# edr.net
KiCad netlist of a schematic drawn in EAGLE
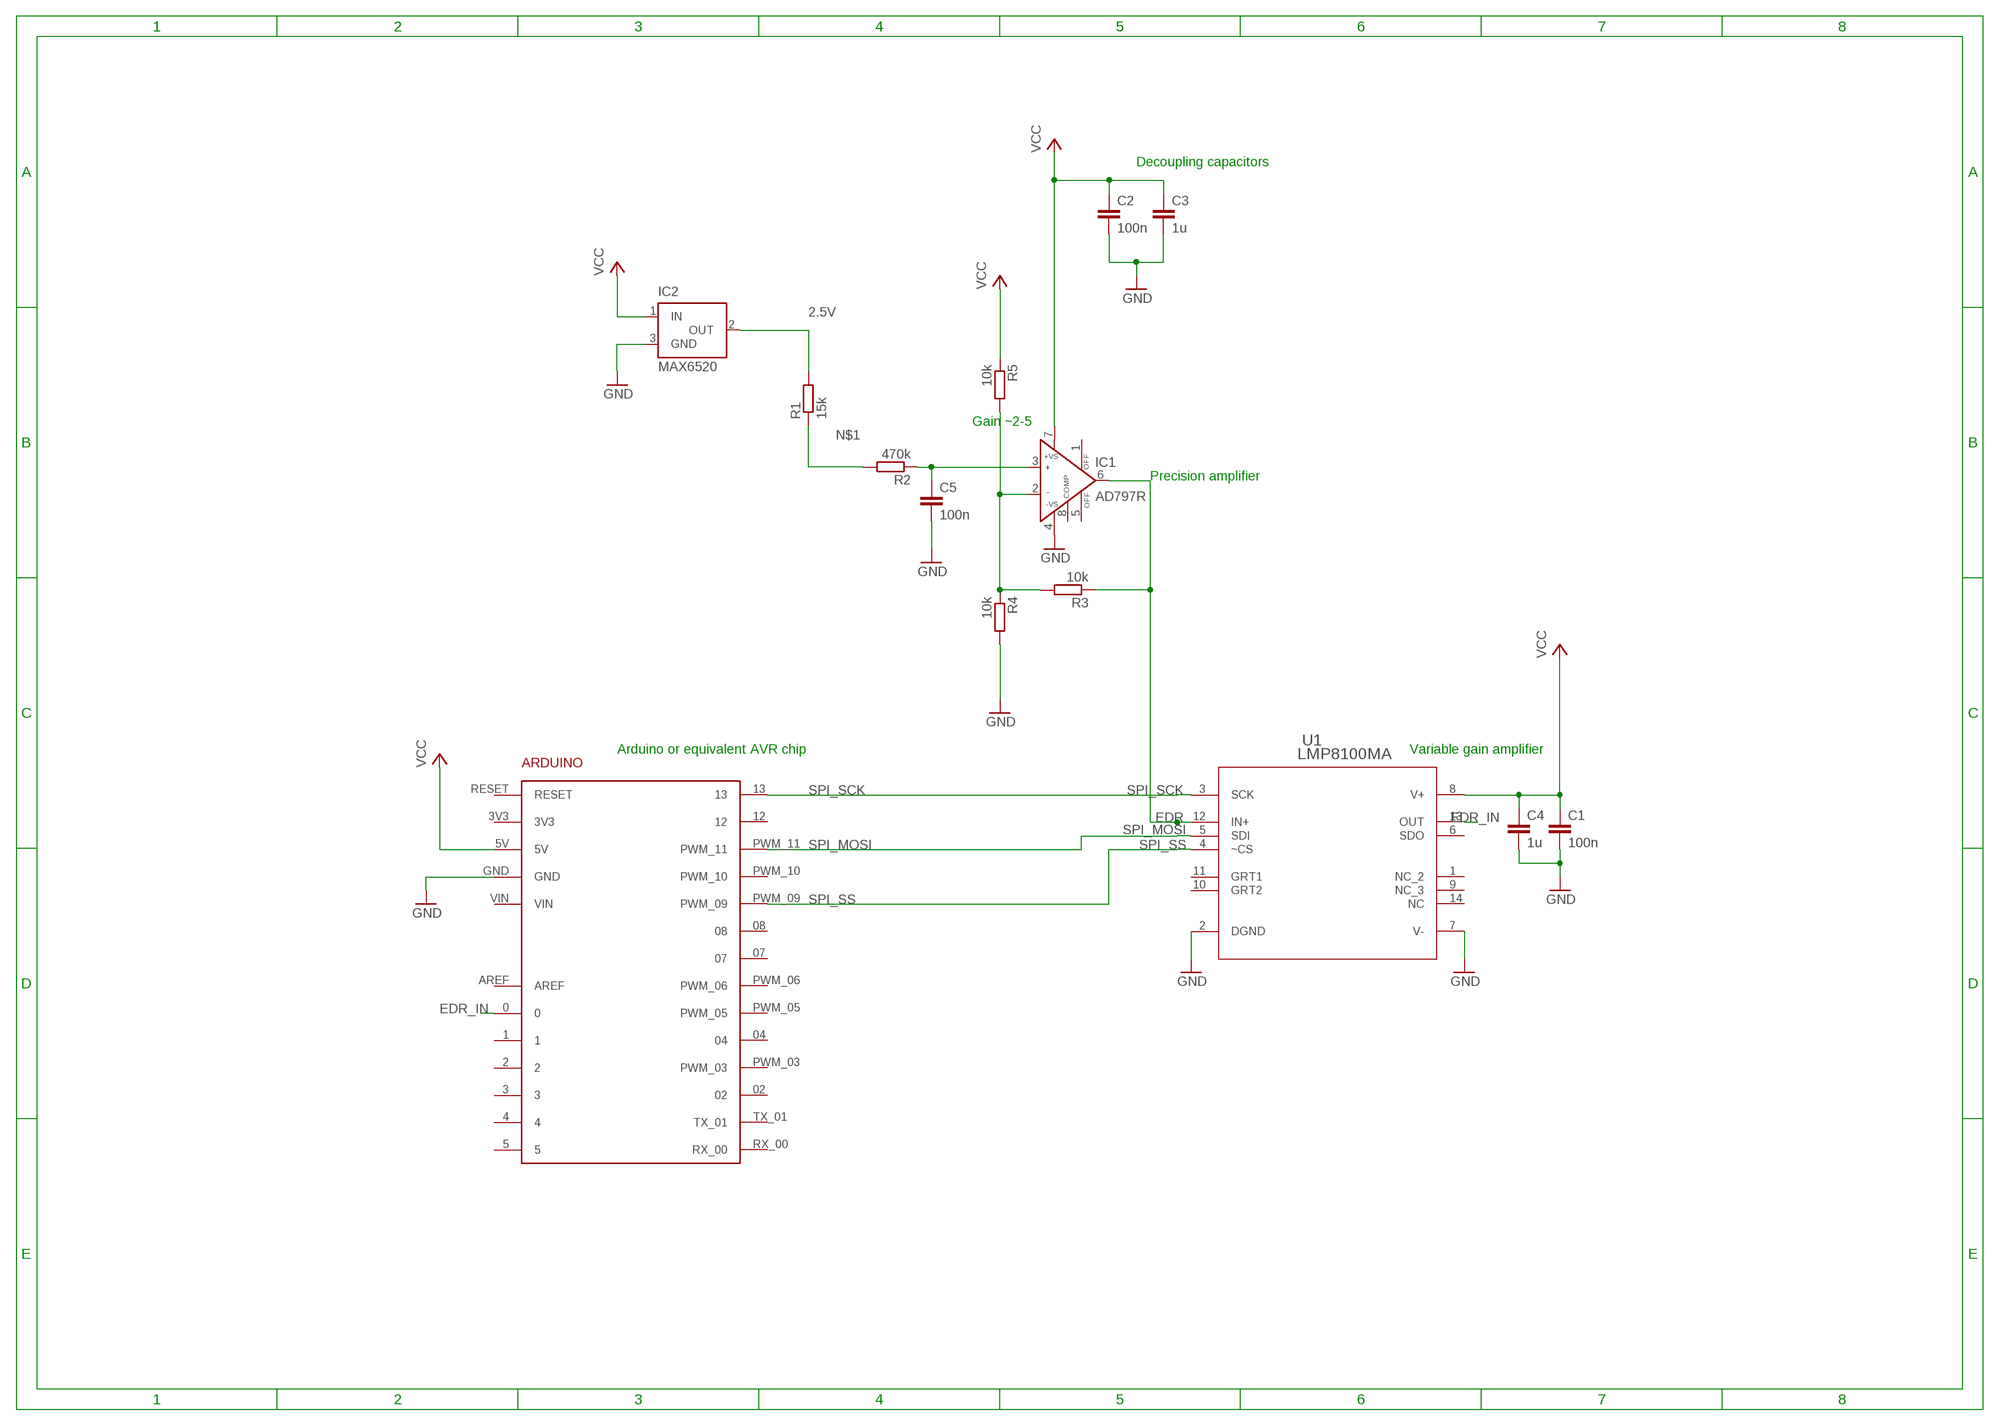
[diagram p0: schematic, sheet 1]

(export (version "E")
  (design (tool "Eeschema 10.0.6"))
  (components
    (comp (ref "ARDUINO1")
      (value "ARDUINO2")
      (footprint "eagle-import:ARDUINO2")
      (libsource (lib "eagle-import") (part "ARDUINO2"))
    )
    (comp (ref "C1")
      (value "100n")
      (footprint "eagle-import:C0603")
      (libsource (lib "eagle-import") (part "C-EUC0603"))
    )
    (comp (ref "C2")
      (value "100n")
      (footprint "eagle-import:C0603")
      (libsource (lib "eagle-import") (part "C-EUC0603"))
    )
    (comp (ref "C3")
      (value "1u")
      (footprint "eagle-import:C0805")
      (libsource (lib "eagle-import") (part "C-EUC0805"))
    )
    (comp (ref "C4")
      (value "1u")
      (footprint "eagle-import:C0805")
      (libsource (lib "eagle-import") (part "C-EUC0805"))
    )
    (comp (ref "C5")
      (value "100n")
      (footprint "eagle-import:C0603")
      (libsource (lib "eagle-import") (part "C-EUC0603"))
    )
    (comp (ref "IC1")
      (value "AD797R")
      (footprint "eagle-import:SO8")
      (fields (field (name "MF") "ALTERA CORPORATION") (field (name "MPN") "AD797ARZ"))
      (libsource (lib "eagle-import") (part "AD797R"))
    )
    (comp (ref "IC2")
      (value "MAX6520")
      (footprint "eagle-import:SOT23")
      (fields (field (name "MF") "MAXIM") (field (name "MPN") "MAX6520EUR-T"))
      (libsource (lib "eagle-import") (part "MAX6520"))
    )
    (comp (ref "R1")
      (value "15k")
      (footprint "eagle-import:R0603")
      (libsource (lib "eagle-import") (part "R-EU_R0603"))
    )
    (comp (ref "R2")
      (value "470k")
      (footprint "eagle-import:R0603")
      (libsource (lib "eagle-import") (part "R-EU_R0603"))
    )
    (comp (ref "R3")
      (value "10k")
      (footprint "eagle-import:R0603")
      (libsource (lib "eagle-import") (part "R-EU_R0603"))
    )
    (comp (ref "R4")
      (value "10k")
      (footprint "eagle-import:R0603")
      (libsource (lib "eagle-import") (part "R-EU_R0603"))
    )
    (comp (ref "R5")
      (value "10k")
      (footprint "eagle-import:R0603")
      (libsource (lib "eagle-import") (part "R-EU_R0603"))
    )
    (comp (ref "U1")
      (value "LMP8100MA")
      (footprint "eagle-import:M14A")
      (libsource (lib "eagle-import") (part "LMP8100MA"))
    )
  )
  (nets
    (net (code "1") (name "/2.5V") (class "Default")
      (node (ref "IC2") (pin "2") (pinfunction "OUT_2") (pintype "output"))
      (node (ref "R1") (pin "2") (pinfunction "2_2") (pintype "passive"))
    )
    (net (code "2") (name "/EDR") (class "Default")
      (node (ref "IC1") (pin "6") (pinfunction "OUT_6") (pintype "output"))
      (node (ref "R3") (pin "1") (pinfunction "1_1") (pintype "passive"))
      (node (ref "U1") (pin "12") (pinfunction "IN+_12") (pintype "input"))
    )
    (net (code "3") (name "/EDR_IN") (class "Default")
      (node (ref "ARDUINO1") (pin "0") (pinfunction "0_0") (pintype "bidirectional"))
      (node (ref "U1") (pin "13") (pinfunction "OUT_13") (pintype "passive"))
    )
    (net (code "4") (name "/N$1") (class "Default")
      (node (ref "R1") (pin "1") (pinfunction "1_1") (pintype "passive"))
      (node (ref "R2") (pin "2") (pinfunction "2_2") (pintype "passive"))
    )
    (net (code "5") (name "/SPI_MOSI") (class "Default")
      (node (ref "ARDUINO1") (pin "PWM_11") (pinfunction "PWM_11_PWM_11") (pintype "bidirectional"))
      (node (ref "U1") (pin "5") (pinfunction "SDI_5") (pintype "input"))
    )
    (net (code "6") (name "/SPI_SCK") (class "Default")
      (node (ref "ARDUINO1") (pin "13") (pinfunction "13_13") (pintype "bidirectional"))
      (node (ref "U1") (pin "3") (pinfunction "SCK_3") (pintype "input"))
    )
    (net (code "7") (name "/SPI_SS") (class "Default")
      (node (ref "ARDUINO1") (pin "PWM_09") (pinfunction "PWM_09_PWM_09") (pintype "bidirectional"))
      (node (ref "U1") (pin "4") (pinfunction "~{CS}_4") (pintype "input"))
    )
    (net (code "8") (name "GND") (class "Default")
      (node (ref "ARDUINO1") (pin "GND") (pinfunction "GND_GND") (pintype "bidirectional"))
      (node (ref "C1") (pin "2") (pinfunction "2_2") (pintype "passive"))
      (node (ref "C2") (pin "2") (pinfunction "2_2") (pintype "passive"))
      (node (ref "C3") (pin "2") (pinfunction "2_2") (pintype "passive"))
      (node (ref "C4") (pin "2") (pinfunction "2_2") (pintype "passive"))
      (node (ref "C5") (pin "2") (pinfunction "2_2") (pintype "passive"))
      (node (ref "IC1") (pin "4") (pinfunction "-VS_4") (pintype "input"))
      (node (ref "IC2") (pin "3") (pinfunction "GND_3") (pintype "power_in"))
      (node (ref "R4") (pin "2") (pinfunction "2_2") (pintype "passive"))
      (node (ref "U1") (pin "2") (pinfunction "DGND_2") (pintype "passive"))
      (node (ref "U1") (pin "7") (pinfunction "V-_7") (pintype "power_in"))
    )
    (net (code "9") (name "Net-(IC1-IN+)") (class "Default")
      (node (ref "C5") (pin "1") (pinfunction "1_1") (pintype "passive"))
      (node (ref "IC1") (pin "3") (pinfunction "IN+_3") (pintype "input"))
      (node (ref "R2") (pin "1") (pinfunction "1_1") (pintype "passive"))
    )
    (net (code "10") (name "Net-(IC1-IN-)") (class "Default")
      (node (ref "IC1") (pin "2") (pinfunction "IN-_2") (pintype "input"))
      (node (ref "R3") (pin "2") (pinfunction "2_2") (pintype "passive"))
      (node (ref "R4") (pin "1") (pinfunction "1_1") (pintype "passive"))
      (node (ref "R5") (pin "2") (pinfunction "2_2") (pintype "passive"))
    )
    (net (code "11") (name "VCC") (class "Default")
      (node (ref "ARDUINO1") (pin "5V") (pinfunction "5V_5V") (pintype "bidirectional"))
      (node (ref "C1") (pin "1") (pinfunction "1_1") (pintype "passive"))
      (node (ref "C2") (pin "1") (pinfunction "1_1") (pintype "passive"))
      (node (ref "C3") (pin "1") (pinfunction "1_1") (pintype "passive"))
      (node (ref "C4") (pin "1") (pinfunction "1_1") (pintype "passive"))
      (node (ref "IC1") (pin "7") (pinfunction "+VS_7") (pintype "input"))
      (node (ref "IC2") (pin "1") (pinfunction "IN_1") (pintype "input"))
      (node (ref "R5") (pin "1") (pinfunction "1_1") (pintype "passive"))
      (node (ref "U1") (pin "8") (pinfunction "V+_8") (pintype "power_in"))
    )
    (net (code "12") (name "unconnected-(ARDUINO1-Pad1)") (class "Default")
      (node (ref "ARDUINO1") (pin "1") (pinfunction "1_1") (pintype "bidirectional"))
    )
    (net (code "13") (name "unconnected-(ARDUINO1-Pad2)") (class "Default")
      (node (ref "ARDUINO1") (pin "2") (pinfunction "2_2") (pintype "bidirectional"))
    )
    (net (code "14") (name "unconnected-(ARDUINO1-Pad02)") (class "Default")
      (node (ref "ARDUINO1") (pin "02") (pinfunction "02_02") (pintype "bidirectional"))
    )
    (net (code "15") (name "unconnected-(ARDUINO1-Pad3)") (class "Default")
      (node (ref "ARDUINO1") (pin "3") (pinfunction "3_3") (pintype "bidirectional"))
    )
    (net (code "16") (name "unconnected-(ARDUINO1-Pad3V3)") (class "Default")
      (node (ref "ARDUINO1") (pin "3V3") (pinfunction "3V3_3V3") (pintype "bidirectional"))
    )
    (net (code "17") (name "unconnected-(ARDUINO1-Pad4)") (class "Default")
      (node (ref "ARDUINO1") (pin "4") (pinfunction "4_4") (pintype "bidirectional"))
    )
    (net (code "18") (name "unconnected-(ARDUINO1-Pad04)") (class "Default")
      (node (ref "ARDUINO1") (pin "04") (pinfunction "04_04") (pintype "bidirectional"))
    )
    (net (code "19") (name "unconnected-(ARDUINO1-Pad5)") (class "Default")
      (node (ref "ARDUINO1") (pin "5") (pinfunction "5_5") (pintype "bidirectional"))
    )
    (net (code "20") (name "unconnected-(ARDUINO1-Pad07)") (class "Default")
      (node (ref "ARDUINO1") (pin "07") (pinfunction "07_07") (pintype "bidirectional"))
    )
    (net (code "21") (name "unconnected-(ARDUINO1-Pad08)") (class "Default")
      (node (ref "ARDUINO1") (pin "08") (pinfunction "08_08") (pintype "bidirectional"))
    )
    (net (code "22") (name "unconnected-(ARDUINO1-Pad12)") (class "Default")
      (node (ref "ARDUINO1") (pin "12") (pinfunction "12_12") (pintype "bidirectional"))
    )
    (net (code "23") (name "unconnected-(ARDUINO1-PadAREF)") (class "Default")
      (node (ref "ARDUINO1") (pin "AREF") (pinfunction "AREF_AREF") (pintype "bidirectional"))
    )
    (net (code "24") (name "unconnected-(ARDUINO1-PadPWM_03)") (class "Default")
      (node (ref "ARDUINO1") (pin "PWM_03") (pinfunction "PWM_03_PWM_03") (pintype "bidirectional"))
    )
    (net (code "25") (name "unconnected-(ARDUINO1-PadPWM_05)") (class "Default")
      (node (ref "ARDUINO1") (pin "PWM_05") (pinfunction "PWM_05_PWM_05") (pintype "bidirectional"))
    )
    (net (code "26") (name "unconnected-(ARDUINO1-PadPWM_06)") (class "Default")
      (node (ref "ARDUINO1") (pin "PWM_06") (pinfunction "PWM_06_PWM_06") (pintype "bidirectional"))
    )
    (net (code "27") (name "unconnected-(ARDUINO1-PadPWM_10)") (class "Default")
      (node (ref "ARDUINO1") (pin "PWM_10") (pinfunction "PWM_10_PWM_10") (pintype "bidirectional"))
    )
    (net (code "28") (name "unconnected-(ARDUINO1-PadRESET)") (class "Default")
      (node (ref "ARDUINO1") (pin "RESET") (pinfunction "RESET_RESET") (pintype "bidirectional"))
    )
    (net (code "29") (name "unconnected-(ARDUINO1-PadRX_00)") (class "Default")
      (node (ref "ARDUINO1") (pin "RX_00") (pinfunction "RX_00_RX_00") (pintype "bidirectional"))
    )
    (net (code "30") (name "unconnected-(ARDUINO1-PadTX_01)") (class "Default")
      (node (ref "ARDUINO1") (pin "TX_01") (pinfunction "TX_01_TX_01") (pintype "bidirectional"))
    )
    (net (code "31") (name "unconnected-(ARDUINO1-PadVIN)") (class "Default")
      (node (ref "ARDUINO1") (pin "VIN") (pinfunction "VIN_VIN") (pintype "bidirectional"))
    )
    (net (code "32") (name "unconnected-(IC1-COMP-Pad8)") (class "Default")
      (node (ref "IC1") (pin "8") (pinfunction "COMP_8") (pintype "passive"))
    )
    (net (code "33") (name "unconnected-(IC1-OFF-Pad1)") (class "Default")
      (node (ref "IC1") (pin "1") (pinfunction "OFF_1") (pintype "passive"))
    )
    (net (code "34") (name "unconnected-(IC1-OFF-Pad5)") (class "Default")
      (node (ref "IC1") (pin "5") (pinfunction "OFF_5") (pintype "passive"))
    )
    (net (code "35") (name "unconnected-(U1-GRT1-Pad11)") (class "Default")
      (node (ref "U1") (pin "11") (pinfunction "GRT1_11") (pintype "passive"))
    )
    (net (code "36") (name "unconnected-(U1-GRT2-Pad10)") (class "Default")
      (node (ref "U1") (pin "10") (pinfunction "GRT2_10") (pintype "passive"))
    )
    (net (code "37") (name "unconnected-(U1-NC-Pad14)") (class "Default")
      (node (ref "U1") (pin "14") (pinfunction "NC_14") (pintype "passive"))
    )
    (net (code "38") (name "unconnected-(U1-NC_2-Pad1)") (class "Default")
      (node (ref "U1") (pin "1") (pinfunction "NC_2_1") (pintype "passive"))
    )
    (net (code "39") (name "unconnected-(U1-NC_3-Pad9)") (class "Default")
      (node (ref "U1") (pin "9") (pinfunction "NC_3_9") (pintype "passive"))
    )
    (net (code "40") (name "unconnected-(U1-SDO-Pad6)") (class "Default")
      (node (ref "U1") (pin "6") (pinfunction "SDO_6") (pintype "output"))
    )
  )
)
